# lab1_zasetskiy_usb_spi.net
KiCad netlist of a schematic drawn in Altium Designer
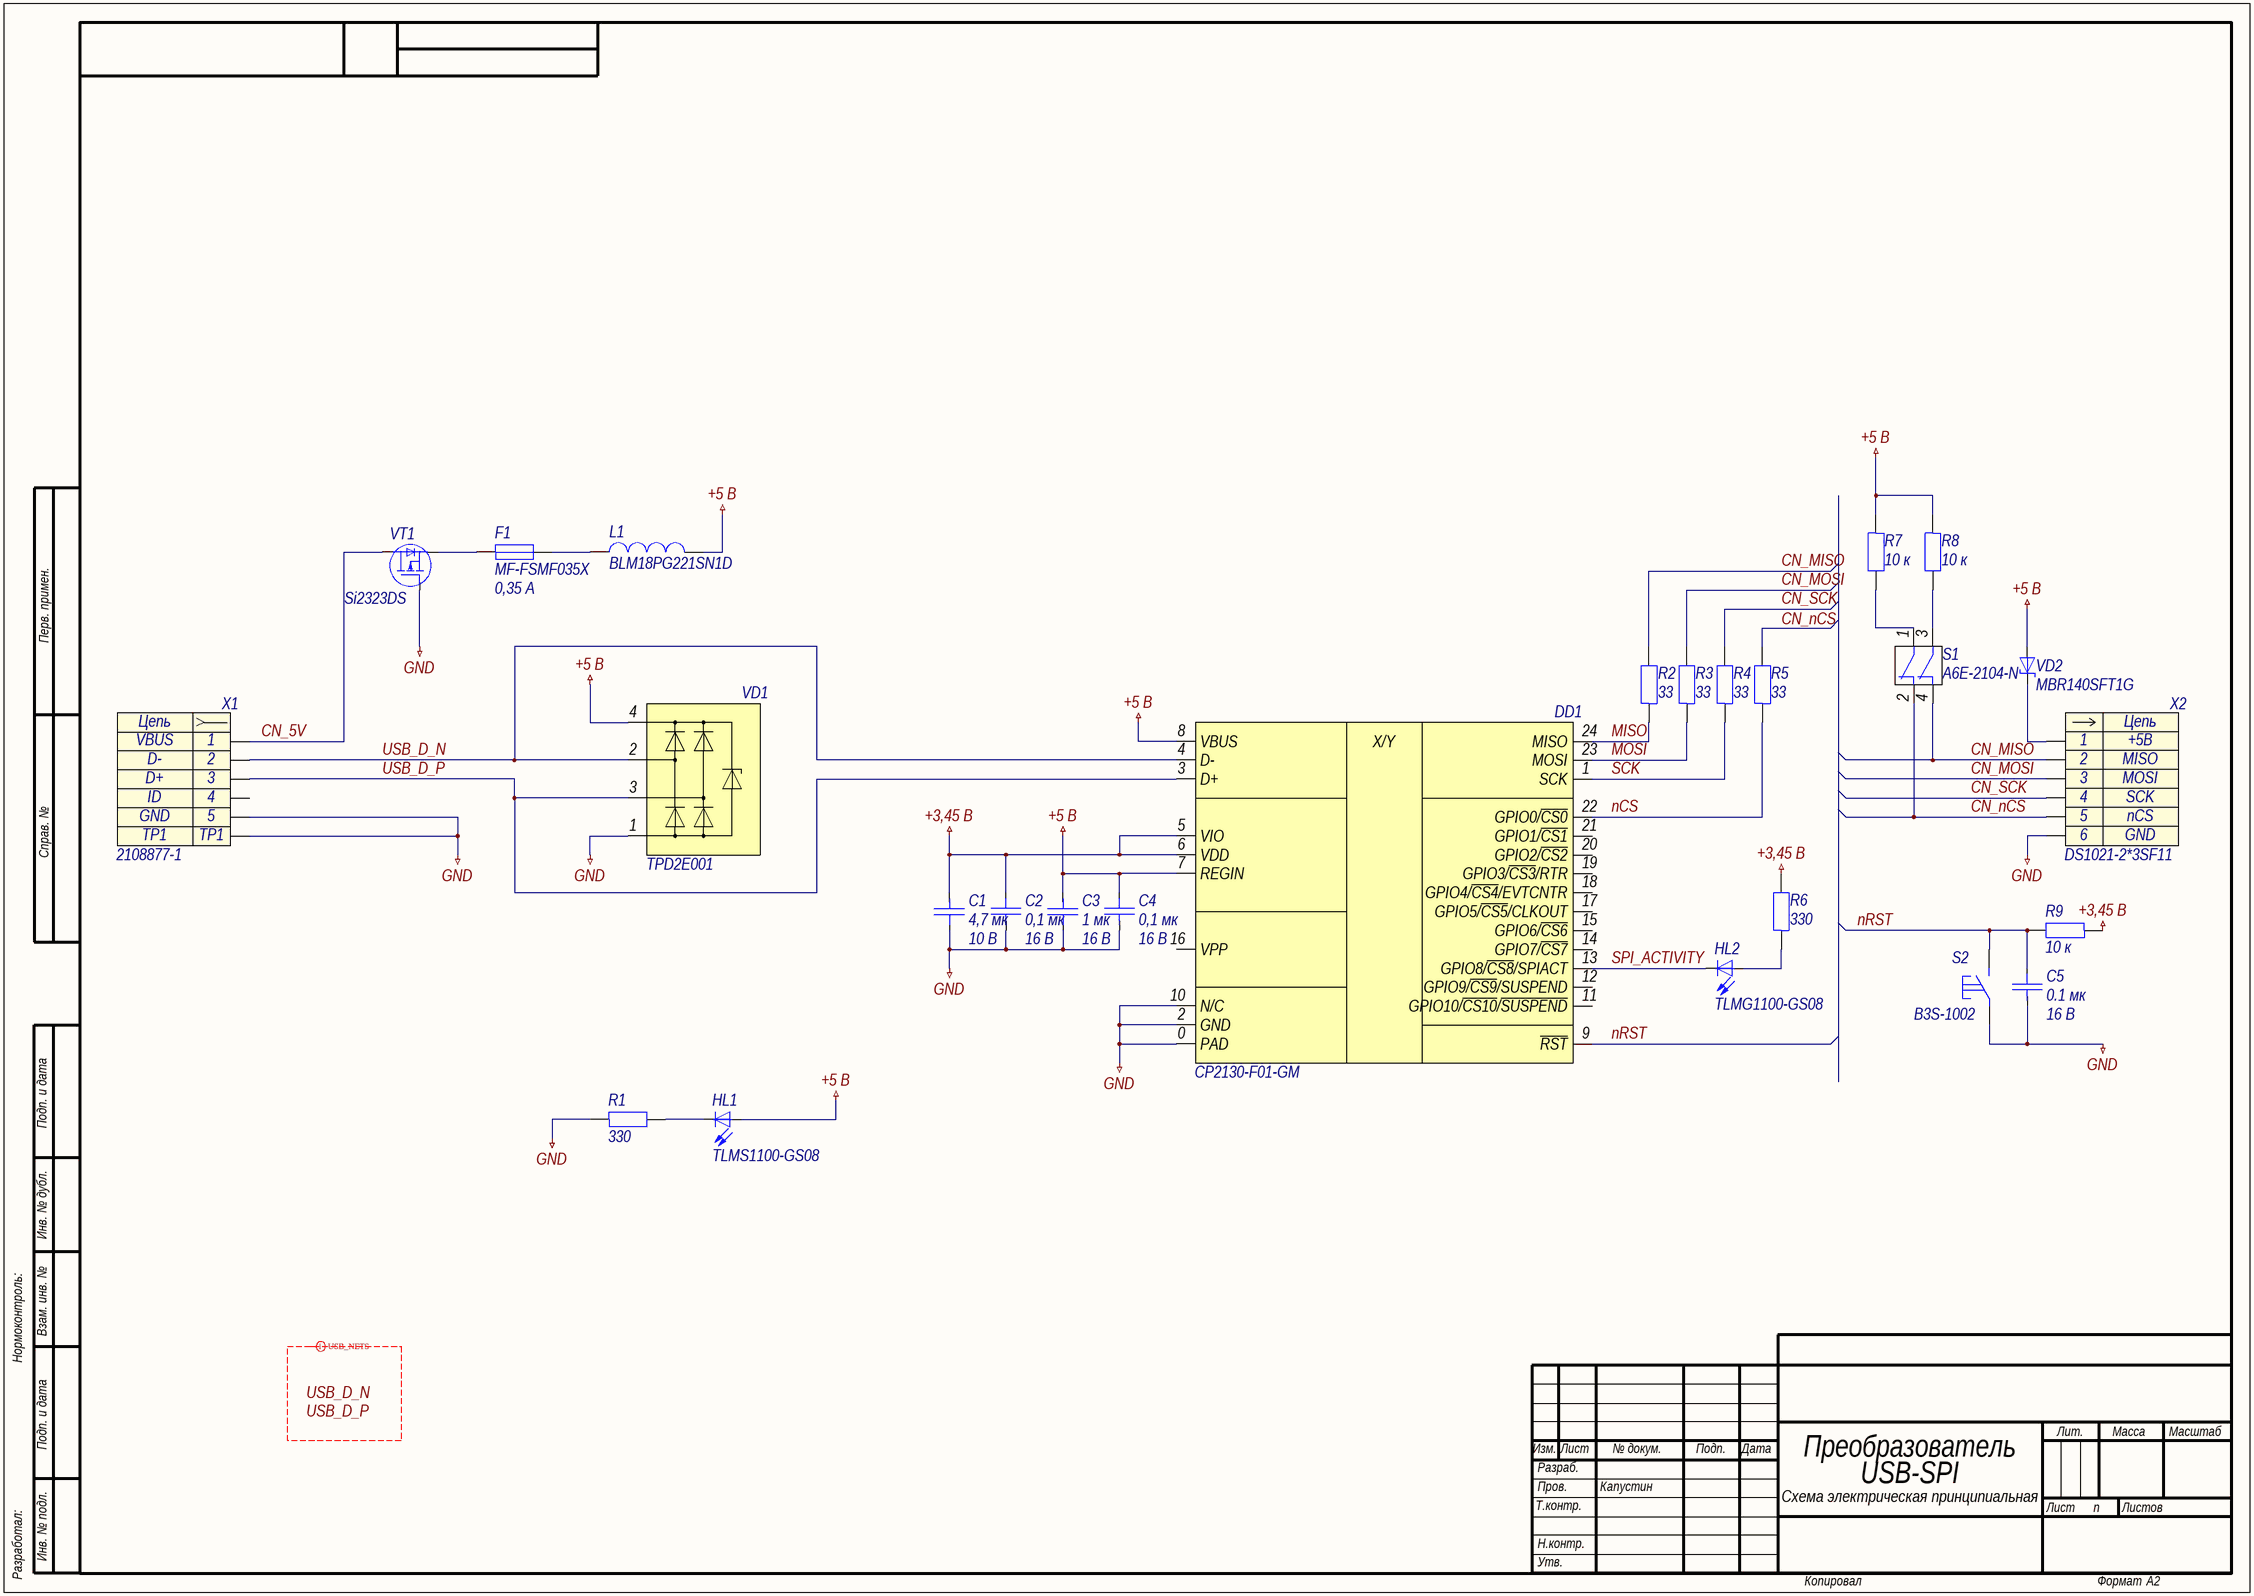
[diagram p0: lab1_zasetskiy_usb_spi.SchDoc]

(export (version "E")
  (design (tool "Eeschema 10.0.6"))
  (components
    (comp (ref "C1")
      (value "4,7 мк")
      (footprint "C0402")
      (description "=Описание")
      (fields (field (name "НАПРЯЖЕНИЕ") "10 В"))
      (libsource (lib "Database_Students") (part "cap"))
    )
    (comp (ref "C2")
      (value "0,1 мк")
      (footprint "C0402")
      (description "=Описание")
      (fields (field (name "НАПРЯЖЕНИЕ") "16 В"))
      (libsource (lib "Database_Students") (part "cap"))
    )
    (comp (ref "C3")
      (value "1 мк")
      (footprint "C0402")
      (description "=Описание")
      (fields (field (name "НАПРЯЖЕНИЕ") "16 В"))
      (libsource (lib "Database_Students") (part "cap"))
    )
    (comp (ref "C4")
      (value "0,1 мк")
      (footprint "C0402")
      (description "=Описание")
      (fields (field (name "НАПРЯЖЕНИЕ") "16 В"))
      (libsource (lib "Database_Students") (part "cap"))
    )
    (comp (ref "C5")
      (value "0.1 мк")
      (footprint "C0402")
      (description "=Описание")
      (fields (field (name "НАПРЯЖЕНИЕ") "16 В"))
      (libsource (lib "Database_Students") (part "cap"))
    )
    (comp (ref "DD1")
      (value "CP2130-F01-GM")
      (footprint "QFN-24-400X400X80")
      (description "=Описание")
      (libsource (lib "Database_Students") (part "CP2130-F01-GM"))
    )
    (comp (ref "F1")
      (value "MF-FSMF035X")
      (footprint "F0603")
      (description "=Описание")
      (fields (field (name "HOLD CURRENT") "0,35 А"))
      (libsource (lib "Database_Students") (part "F-COMMON"))
    )
    (comp (ref "HL1")
      (value "TLMS1100-GS08")
      (footprint "LED")
      (description "=Описание")
      (libsource (lib "Database_Students") (part "led"))
    )
    (comp (ref "HL2")
      (value "TLMG1100-GS08")
      (footprint "LED_GREEN")
      (description "=Описание")
      (libsource (lib "Database_Students") (part "led"))
    )
    (comp (ref "L1")
      (value "BLM18PG221SN1D")
      (footprint "BLM-2-0603")
      (description "=Описание")
      (libsource (lib "Database_Students") (part "FERRITE-BEAD"))
    )
    (comp (ref "R1")
      (value "330")
      (footprint "R0603")
      (description "=Описание")
      (libsource (lib "Database_Students") (part "R-0.063W"))
    )
    (comp (ref "R2")
      (value "33")
      (footprint "R0603")
      (description "=Описание")
      (libsource (lib "Database_Students") (part "R-0.063W"))
    )
    (comp (ref "R3")
      (value "33")
      (footprint "R0603")
      (description "=Описание")
      (libsource (lib "Database_Students") (part "R-0.063W"))
    )
    (comp (ref "R4")
      (value "33")
      (footprint "R0603")
      (description "=Описание")
      (libsource (lib "Database_Students") (part "R-0.063W"))
    )
    (comp (ref "R5")
      (value "33")
      (footprint "R0603")
      (description "=Описание")
      (libsource (lib "Database_Students") (part "R-0.063W"))
    )
    (comp (ref "R6")
      (value "330")
      (footprint "R0603")
      (description "=Описание")
      (libsource (lib "Database_Students") (part "R-0.063W"))
    )
    (comp (ref "R7")
      (value "10 к")
      (footprint "R0603")
      (description "=Описание")
      (libsource (lib "Database_Students") (part "R-0.063W"))
    )
    (comp (ref "R8")
      (value "10 к")
      (footprint "R0603")
      (description "=Описание")
      (libsource (lib "Database_Students") (part "R-0.063W"))
    )
    (comp (ref "R9")
      (value "10 к")
      (footprint "R0603")
      (description "=Описание")
      (libsource (lib "Database_Students") (part "R-0.063W"))
    )
    (comp (ref "S1")
      (value "A6E-2104-N")
      (footprint "A6E-2104-N")
      (description "=Описание")
      (libsource (lib "Database_Students") (part "SWITCH-4C"))
    )
    (comp (ref "S2")
      (value "B3S-1002")
      (footprint "B3S-1002")
      (description "=Описание")
      (libsource (lib "Database_Students") (part "BUTTON"))
    )
    (comp (ref "VD1")
      (value "TPD2E001")
      (footprint "SOP")
      (libsource (lib "Database_Students") (part "tpd2e001"))
    )
    (comp (ref "VD2")
      (value "MBR140SFT1G")
      (footprint "DIODE")
      (description "=Описание")
      (libsource (lib "Database_Students") (part "MBR140SFT1G"))
    )
    (comp (ref "VT1")
      (value "Si2323DS")
      (footprint "SOT-23-3")
      (description "=Описание")
      (libsource (lib "Database_Students") (part "MOSFET-P-1G-1S-1D"))
    )
    (comp (ref "X1")
      (value "2108877-1")
      (footprint "2108877-1")
      (description "=Описание")
      (libsource (lib "Database_Students") (part "MICRO_USB-B"))
    )
    (comp (ref "X2")
      (value "DS1021-2*3SF11")
      (footprint "PLS_2.54_2x3")
      (description "=Описание")
      (libsource (lib "Database_Students") (part "DS1021-2*3SF11"))
    )
  )
  (nets
    (net (code "1") (name "+3,45 В") (class "Default")
      (node (ref "C1") (pin "2") (pinfunction "2_2") (pintype "passive"))
      (node (ref "C2") (pin "1") (pinfunction "1_1") (pintype "passive"))
      (node (ref "DD1") (pin "5") (pinfunction "VIO_5") (pintype "passive"))
      (node (ref "DD1") (pin "6") (pinfunction "VDD_6") (pintype "passive"))
      (node (ref "R6") (pin "2") (pinfunction "2_2") (pintype "passive"))
      (node (ref "R9") (pin "1") (pinfunction "1_1") (pintype "passive"))
    )
    (net (code "2") (name "+5 В") (class "Default")
      (node (ref "C3") (pin "2") (pinfunction "2_2") (pintype "passive"))
      (node (ref "C4") (pin "1") (pinfunction "1_1") (pintype "passive"))
      (node (ref "DD1") (pin "7") (pinfunction "REGIN_7") (pintype "passive"))
      (node (ref "DD1") (pin "8") (pinfunction "VBUS_8") (pintype "passive"))
      (node (ref "HL1") (pin "1") (pinfunction "A_1") (pintype "passive"))
      (node (ref "L1") (pin "2") (pinfunction "2_2") (pintype "passive"))
      (node (ref "R7") (pin "1") (pinfunction "1_1") (pintype "passive"))
      (node (ref "R8") (pin "1") (pinfunction "1_1") (pintype "passive"))
      (node (ref "VD1") (pin "4") (pintype "passive"))
      (node (ref "VD2") (pin "1") (pinfunction "A_1") (pintype "passive"))
    )
    (net (code "3") (name "/CN_5V") (class "Default")
      (node (ref "VT1") (pin "3") (pinfunction "D_3") (pintype "passive"))
      (node (ref "X1") (pin "1") (pinfunction "1_1") (pintype "passive"))
    )
    (net (code "4") (name "/CN_MISO") (class "Default")
      (node (ref "R2") (pin "2") (pinfunction "2_2") (pintype "passive"))
      (node (ref "S1") (pin "4") (pinfunction "4_4") (pintype "passive"))
      (node (ref "X2") (pin "2") (pinfunction "2_2") (pintype "passive"))
    )
    (net (code "5") (name "/CN_MOSI") (class "Default")
      (node (ref "R3") (pin "2") (pinfunction "2_2") (pintype "passive"))
      (node (ref "X2") (pin "3") (pinfunction "3_3") (pintype "passive"))
    )
    (net (code "6") (name "/CN_SCK") (class "Default")
      (node (ref "R4") (pin "2") (pinfunction "2_2") (pintype "passive"))
      (node (ref "X2") (pin "4") (pinfunction "4_4") (pintype "passive"))
    )
    (net (code "7") (name "/CN_nCS") (class "Default")
      (node (ref "S1") (pin "2") (pinfunction "2_2") (pintype "passive"))
      (node (ref "X2") (pin "5") (pinfunction "5_5") (pintype "passive"))
    )
    (net (code "8") (name "/MISO") (class "Default")
      (node (ref "DD1") (pin "24") (pinfunction "MISO_24") (pintype "passive"))
      (node (ref "R2") (pin "1") (pinfunction "1_1") (pintype "passive"))
    )
    (net (code "9") (name "/MOSI") (class "Default")
      (node (ref "DD1") (pin "23") (pinfunction "MOSI_23") (pintype "passive"))
      (node (ref "R3") (pin "1") (pinfunction "1_1") (pintype "passive"))
    )
    (net (code "10") (name "/SCK") (class "Default")
      (node (ref "DD1") (pin "1") (pinfunction "SCK_1") (pintype "passive"))
      (node (ref "R4") (pin "1") (pinfunction "1_1") (pintype "passive"))
    )
    (net (code "11") (name "/SPI_ACTIVITY") (class "Default")
      (node (ref "DD1") (pin "13") (pinfunction "GPIO8/~{CS8}/SPIACT_13") (pintype "passive"))
      (node (ref "HL2") (pin "2") (pinfunction "K_2") (pintype "passive"))
    )
    (net (code "12") (name "/USB_D_N") (class "Default")
      (node (ref "DD1") (pin "4") (pinfunction "D-_4") (pintype "passive"))
      (node (ref "VD1") (pin "2") (pintype "passive"))
      (node (ref "X1") (pin "2") (pinfunction "2_2") (pintype "passive"))
    )
    (net (code "13") (name "/USB_D_P") (class "Default")
      (node (ref "DD1") (pin "3") (pinfunction "D+_3") (pintype "passive"))
      (node (ref "VD1") (pin "3") (pintype "passive"))
      (node (ref "X1") (pin "3") (pinfunction "3_3") (pintype "passive"))
    )
    (net (code "14") (name "/nCS") (class "Default")
      (node (ref "DD1") (pin "22") (pinfunction "GPIO0/~{CS0}_22") (pintype "passive"))
      (node (ref "R5") (pin "1") (pinfunction "1_1") (pintype "passive"))
    )
    (net (code "15") (name "/nRST") (class "Default")
      (node (ref "C5") (pin "1") (pinfunction "1_1") (pintype "passive"))
      (node (ref "DD1") (pin "9") (pinfunction "~{RST}_9") (pintype "passive"))
      (node (ref "R9") (pin "2") (pinfunction "2_2") (pintype "passive"))
      (node (ref "S2") (pin "2") (pinfunction "2_2") (pintype "passive"))
    )
    (net (code "16") (name "GND") (class "Default")
      (node (ref "C1") (pin "1") (pinfunction "1_1") (pintype "passive"))
      (node (ref "C2") (pin "2") (pinfunction "2_2") (pintype "passive"))
      (node (ref "C3") (pin "1") (pinfunction "1_1") (pintype "passive"))
      (node (ref "C4") (pin "2") (pinfunction "2_2") (pintype "passive"))
      (node (ref "C5") (pin "2") (pinfunction "2_2") (pintype "passive"))
      (node (ref "DD1") (pin "0") (pinfunction "PAD_0") (pintype "passive"))
      (node (ref "DD1") (pin "10") (pinfunction "N/C_10") (pintype "passive"))
      (node (ref "DD1") (pin "2") (pinfunction "GND_2") (pintype "passive"))
      (node (ref "R1") (pin "1") (pinfunction "1_1") (pintype "passive"))
      (node (ref "S2") (pin "1") (pinfunction "1_1") (pintype "passive"))
      (node (ref "VD1") (pin "1") (pintype "passive"))
      (node (ref "VT1") (pin "1") (pinfunction "G_1") (pintype "passive"))
      (node (ref "X1") (pin "5") (pinfunction "5_5") (pintype "passive"))
      (node (ref "X1") (pin "TP1") (pinfunction "TP1_TP1") (pintype "passive"))
      (node (ref "X2") (pin "6") (pinfunction "6_6") (pintype "passive"))
    )
    (net (code "17") (name "Net-(F1-Pad2)") (class "Default")
      (node (ref "F1") (pin "2") (pinfunction "2_2") (pintype "passive"))
      (node (ref "L1") (pin "1") (pinfunction "1_1") (pintype "passive"))
    )
    (net (code "18") (name "Net-(HL1-K)") (class "Default")
      (node (ref "HL1") (pin "2") (pinfunction "K_2") (pintype "passive"))
      (node (ref "R1") (pin "2") (pinfunction "2_2") (pintype "passive"))
    )
    (net (code "19") (name "Net-(HL2-A)") (class "Default")
      (node (ref "HL2") (pin "1") (pinfunction "A_1") (pintype "passive"))
      (node (ref "R6") (pin "1") (pinfunction "1_1") (pintype "passive"))
    )
    (net (code "20") (name "Net-(R7-Pad2)") (class "Default")
      (node (ref "R7") (pin "2") (pinfunction "2_2") (pintype "passive"))
      (node (ref "S1") (pin "1") (pinfunction "1_1") (pintype "passive"))
    )
    (net (code "21") (name "Net-(R8-Pad2)") (class "Default")
      (node (ref "R8") (pin "2") (pinfunction "2_2") (pintype "passive"))
      (node (ref "S1") (pin "3") (pinfunction "3_3") (pintype "passive"))
    )
    (net (code "22") (name "Net-(VD2-K)") (class "Default")
      (node (ref "VD2") (pin "2") (pinfunction "K_2") (pintype "passive"))
      (node (ref "X2") (pin "1") (pinfunction "1_1") (pintype "passive"))
    )
    (net (code "23") (name "Net-(VT1-S)") (class "Default")
      (node (ref "F1") (pin "1") (pinfunction "1_1") (pintype "passive"))
      (node (ref "VT1") (pin "2") (pinfunction "S_2") (pintype "passive"))
    )
    (net (code "24") (name "unconnected-(DD1-GPIO1{slash}~{CS1}-Pad21)") (class "Default")
      (node (ref "DD1") (pin "21") (pinfunction "GPIO1/~{CS1}_21") (pintype "passive"))
    )
    (net (code "25") (name "unconnected-(DD1-GPIO2{slash}~{CS2}-Pad20)") (class "Default")
      (node (ref "DD1") (pin "20") (pinfunction "GPIO2/~{CS2}_20") (pintype "passive"))
    )
    (net (code "26") (name "unconnected-(DD1-GPIO3{slash}~{CS3}{slash}RTR-Pad19)") (class "Default")
      (node (ref "DD1") (pin "19") (pinfunction "GPIO3/~{CS3}/RTR_19") (pintype "passive"))
    )
    (net (code "27") (name "unconnected-(DD1-GPIO4{slash}~{CS4}{slash}EVTCNTR-Pad18)") (class "Default")
      (node (ref "DD1") (pin "18") (pinfunction "GPIO4/~{CS4}/EVTCNTR_18") (pintype "passive"))
    )
    (net (code "28") (name "unconnected-(DD1-GPIO5{slash}~{CS5}{slash}CLKOUT-Pad17)") (class "Default")
      (node (ref "DD1") (pin "17") (pinfunction "GPIO5/~{CS5}/CLKOUT_17") (pintype "passive"))
    )
    (net (code "29") (name "unconnected-(DD1-GPIO6{slash}~{CS6}-Pad15)") (class "Default")
      (node (ref "DD1") (pin "15") (pinfunction "GPIO6/~{CS6}_15") (pintype "passive"))
    )
    (net (code "30") (name "unconnected-(DD1-GPIO7{slash}~{CS7}-Pad14)") (class "Default")
      (node (ref "DD1") (pin "14") (pinfunction "GPIO7/~{CS7}_14") (pintype "passive"))
    )
    (net (code "31") (name "unconnected-(DD1-GPIO9{slash}~{CS9}{slash}SUSPEND-Pad12)") (class "Default")
      (node (ref "DD1") (pin "12") (pinfunction "GPIO9/~{CS9}/SUSPEND_12") (pintype "passive"))
    )
    (net (code "32") (name "unconnected-(DD1-GPIO10{slash}~{CS10}{slash}~{SUSPEND}-Pad11)") (class "Default")
      (node (ref "DD1") (pin "11") (pinfunction "GPIO10/~{CS10}/~{SUSPEND}_11") (pintype "passive"))
    )
    (net (code "33") (name "unconnected-(DD1-VPP-Pad16)") (class "Default")
      (node (ref "DD1") (pin "16") (pinfunction "VPP_16") (pintype "passive"))
    )
    (net (code "34") (name "unconnected-(R5-Pad2)") (class "Default")
      (node (ref "R5") (pin "2") (pinfunction "2_2") (pintype "passive"))
    )
    (net (code "35") (name "unconnected-(X1-Pad4)") (class "Default")
      (node (ref "X1") (pin "4") (pinfunction "4_4") (pintype "passive"))
    )
  )
)
